# C64_AV-Adaptor.net
KiCad netlist of a schematic drawn in EAGLE
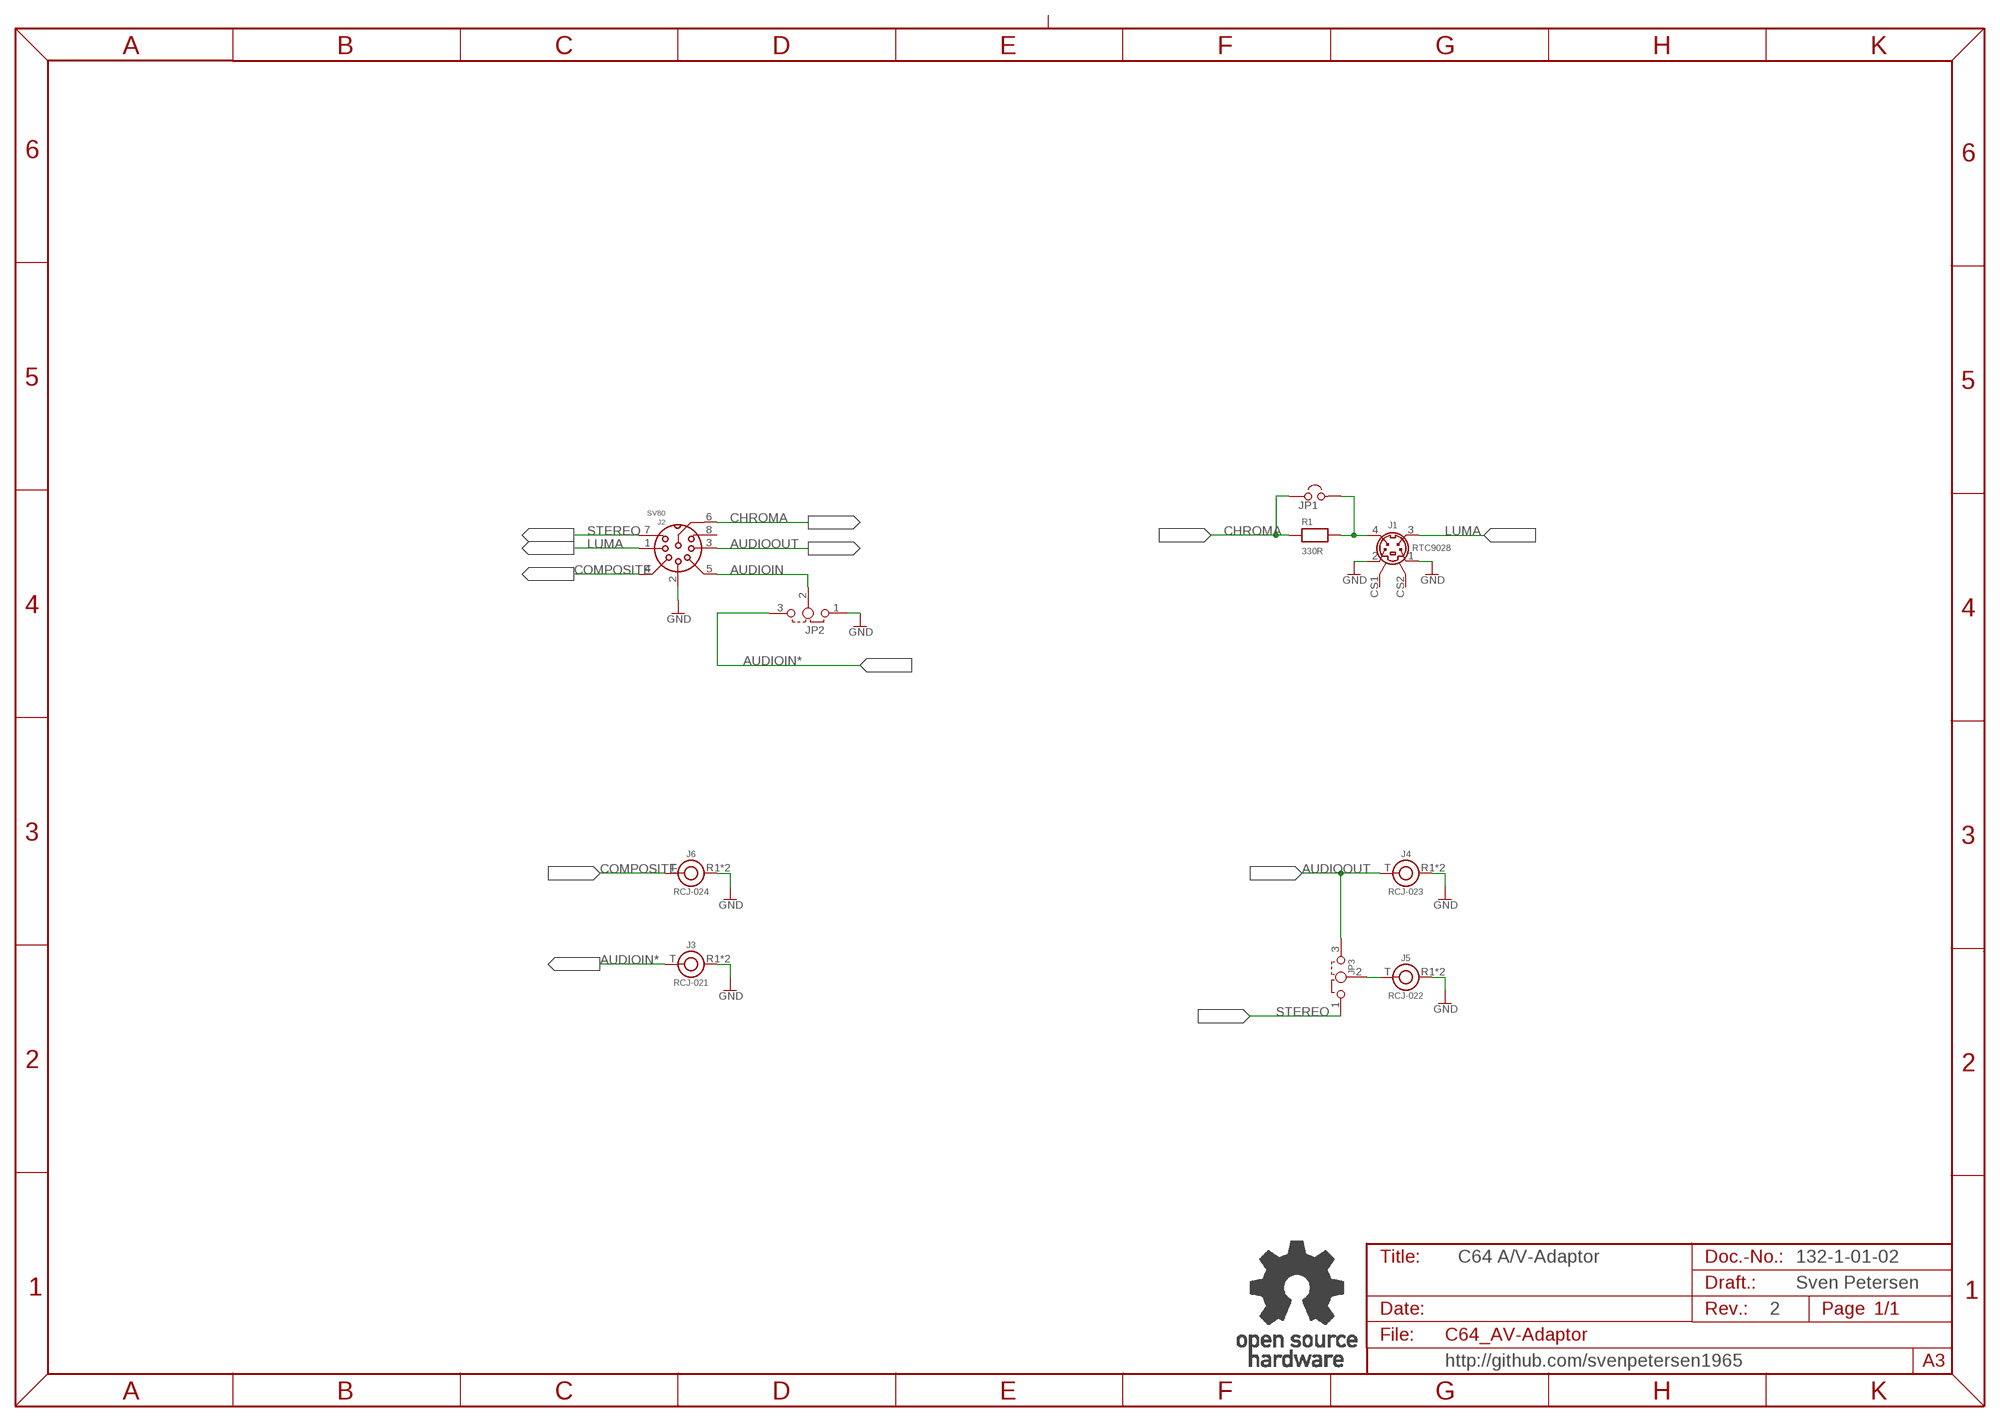
[diagram p0: schematic, sheet 1]

(export (version "E")
  (design (tool "Eeschema 10.0.6"))
  (components
    (comp (ref "J1")
      (value "RTC9028")
      (footprint "eagle-import:MINIDIN4_V")
      (libsource (lib "eagle-import") (part "RTC9028"))
    )
    (comp (ref "J2")
      (value "SV80")
      (footprint "eagle-import:SV80_INNER")
      (libsource (lib "eagle-import") (part "SV80"))
    )
    (comp (ref "J3")
      (value "RCJ-021")
      (footprint "eagle-import:RCJ-02X")
      (libsource (lib "eagle-import") (part "RCJ-02X"))
    )
    (comp (ref "J4")
      (value "RCJ-023")
      (footprint "eagle-import:RCJ-02X")
      (libsource (lib "eagle-import") (part "RCJ-02X"))
    )
    (comp (ref "J5")
      (value "RCJ-022")
      (footprint "eagle-import:RCJ-02X")
      (libsource (lib "eagle-import") (part "RCJ-02X"))
    )
    (comp (ref "J6")
      (value "RCJ-024")
      (footprint "eagle-import:RCJ-02X")
      (libsource (lib "eagle-import") (part "RCJ-02X"))
    )
    (comp (ref "JP1")
      (value "JUMPER")
      (footprint "eagle-import:1X02")
      (libsource (lib "eagle-import") (part "JUMPER"))
    )
    (comp (ref "JP2")
      (value "DJUMPER")
      (footprint "eagle-import:1X03")
      (libsource (lib "eagle-import") (part "DJUMPER"))
    )
    (comp (ref "JP3")
      (value "DJUMPER")
      (footprint "eagle-import:1X03")
      (libsource (lib "eagle-import") (part "DJUMPER"))
    )
    (comp (ref "R1")
      (value "330R")
      (footprint "eagle-import:R-10")
      (libsource (lib "eagle-import") (part "RES04"))
    )
    (comp (ref "U$25")
      (value "OPEN_SOURCE_HW")
      (footprint "eagle-import:OPENHW")
      (libsource (lib "eagle-import") (part "OPEN_SOURCE_HW"))
    )
  )
  (nets
    (net (code "1") (name "/AUDIOIN") (class "Default")
      (node (ref "J2") (pin "5") (pinfunction "5_5") (pintype "bidirectional"))
      (node (ref "JP2") (pin "2") (pinfunction "2_2") (pintype "bidirectional"))
    )
    (net (code "2") (name "/AUDIOIN*") (class "Default")
      (node (ref "J3") (pin "T") (pinfunction "T_T") (pintype "bidirectional"))
      (node (ref "JP2") (pin "3") (pinfunction "3_3") (pintype "bidirectional"))
    )
    (net (code "3") (name "/AUDIOOUT") (class "Default")
      (node (ref "J2") (pin "3") (pinfunction "3_3") (pintype "bidirectional"))
      (node (ref "J4") (pin "T") (pinfunction "T_T") (pintype "bidirectional"))
      (node (ref "JP3") (pin "3") (pinfunction "3_3") (pintype "bidirectional"))
    )
    (net (code "4") (name "/CHROMA") (class "Default")
      (node (ref "J2") (pin "6") (pinfunction "6_6") (pintype "bidirectional"))
      (node (ref "JP1") (pin "1") (pinfunction "1_1") (pintype "bidirectional"))
      (node (ref "R1") (pin "1") (pinfunction "1_1") (pintype "passive"))
    )
    (net (code "5") (name "/COMPOSITE") (class "Default")
      (node (ref "J2") (pin "4") (pinfunction "4_4") (pintype "bidirectional"))
      (node (ref "J6") (pin "T") (pinfunction "T_T") (pintype "bidirectional"))
    )
    (net (code "6") (name "/LUMA") (class "Default")
      (node (ref "J1") (pin "3") (pinfunction "3_3") (pintype "bidirectional"))
      (node (ref "J2") (pin "1") (pinfunction "1_1") (pintype "bidirectional"))
    )
    (net (code "7") (name "/STEREO") (class "Default")
      (node (ref "J2") (pin "7") (pinfunction "7_7") (pintype "bidirectional"))
      (node (ref "JP3") (pin "1") (pinfunction "1_1") (pintype "bidirectional"))
    )
    (net (code "8") (name "GND") (class "Default")
      (node (ref "J1") (pin "1") (pinfunction "1_1") (pintype "bidirectional"))
      (node (ref "J1") (pin "2") (pinfunction "2_2") (pintype "bidirectional"))
      (node (ref "J2") (pin "2") (pinfunction "2_2") (pintype "bidirectional"))
      (node (ref "J3") (pin "R1") (pinfunction "R_R1") (pintype "bidirectional"))
      (node (ref "J3") (pin "R2") (pinfunction "R_R2") (pintype "bidirectional"))
      (node (ref "J4") (pin "R1") (pinfunction "R_R1") (pintype "bidirectional"))
      (node (ref "J4") (pin "R2") (pinfunction "R_R2") (pintype "bidirectional"))
      (node (ref "J5") (pin "R1") (pinfunction "R_R1") (pintype "bidirectional"))
      (node (ref "J5") (pin "R2") (pinfunction "R_R2") (pintype "bidirectional"))
      (node (ref "J6") (pin "R1") (pinfunction "R_R1") (pintype "bidirectional"))
      (node (ref "J6") (pin "R2") (pinfunction "R_R2") (pintype "bidirectional"))
      (node (ref "JP2") (pin "1") (pinfunction "1_1") (pintype "bidirectional"))
    )
    (net (code "9") (name "Net-(J1-Pad4)") (class "Default")
      (node (ref "J1") (pin "4") (pinfunction "4_4") (pintype "bidirectional"))
      (node (ref "JP1") (pin "2") (pinfunction "2_2") (pintype "bidirectional"))
      (node (ref "R1") (pin "2") (pinfunction "2_2") (pintype "passive"))
    )
    (net (code "10") (name "Net-(J5-PadT)") (class "Default")
      (node (ref "J5") (pin "T") (pinfunction "T_T") (pintype "bidirectional"))
      (node (ref "JP3") (pin "2") (pinfunction "2_2") (pintype "bidirectional"))
    )
    (net (code "11") (name "unconnected-(J1-PadCS1)") (class "Default")
      (node (ref "J1") (pin "CS1") (pinfunction "CS1_CS1") (pintype "bidirectional"))
    )
    (net (code "12") (name "unconnected-(J1-PadCS2)") (class "Default")
      (node (ref "J1") (pin "CS2") (pinfunction "CS2_CS2") (pintype "bidirectional"))
    )
    (net (code "13") (name "unconnected-(J2-Pad8)") (class "Default")
      (node (ref "J2") (pin "8") (pinfunction "8_8") (pintype "bidirectional"))
    )
  )
)
